# DemoCatV3.net
KiCad netlist of a schematic drawn in Altium Designer
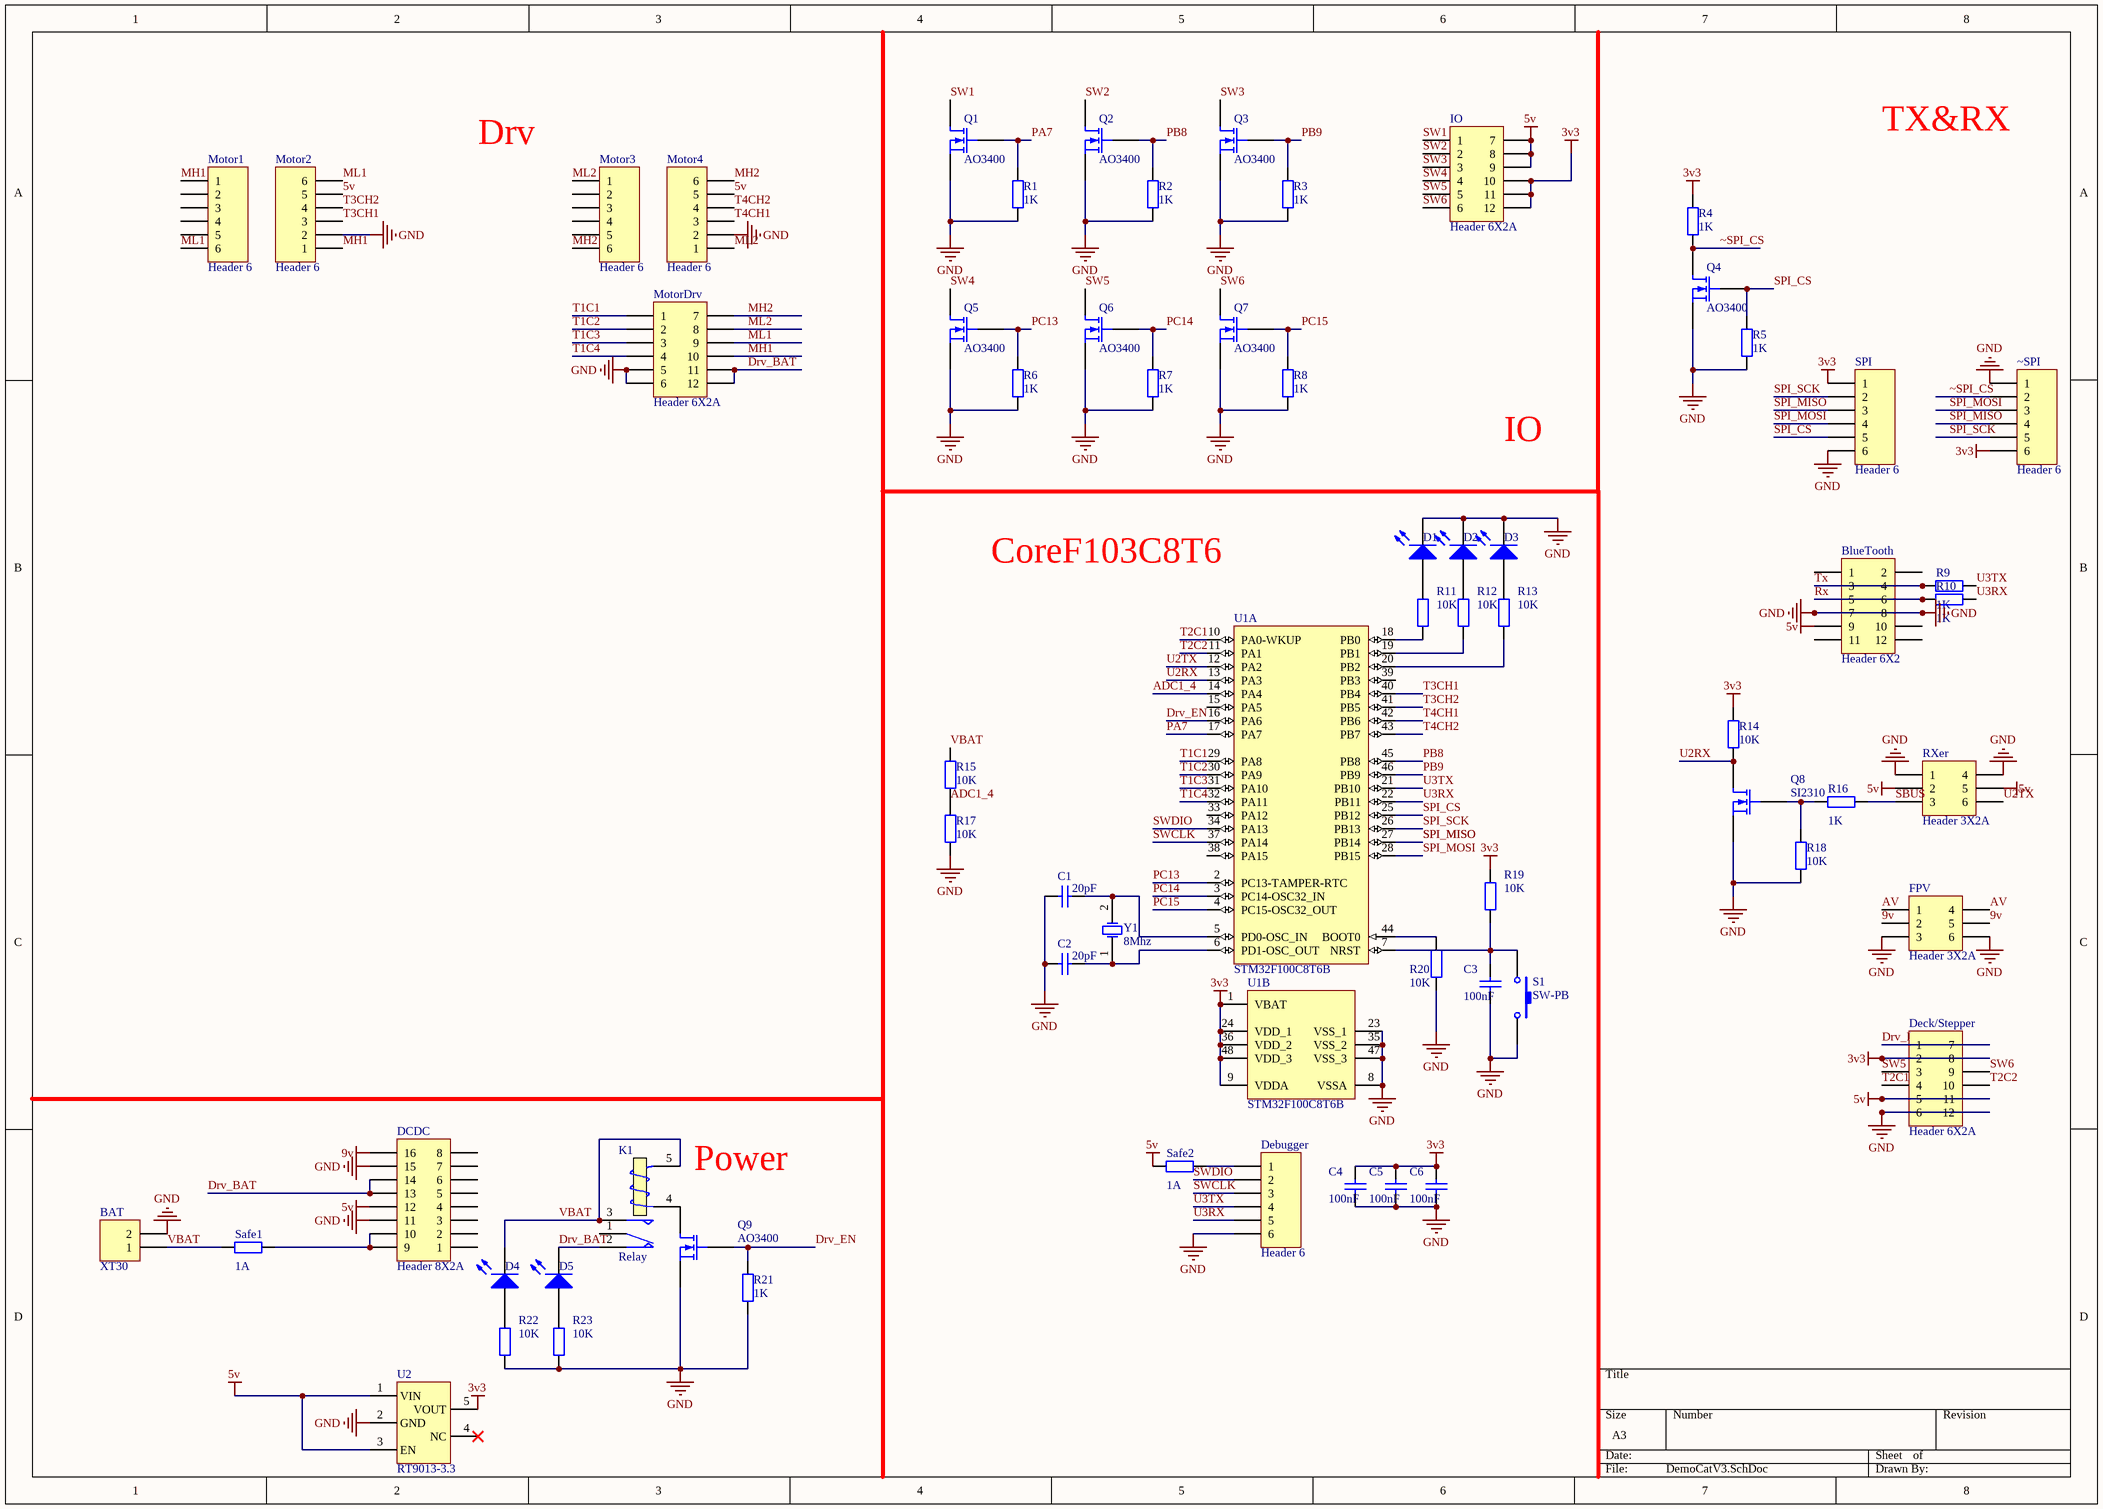
[diagram p0: DemoCatV3.SchDoc]

(export (version "E")
  (design (tool "Eeschema 10.0.6"))
  (components
    (comp (ref "BAT")
      (value "XT30")
      (footprint "XT30-IN-W")
      (description "Header, 2-Pin")
      (fields (field (name "PUBLISHER") "Altium Limited"))
      (libsource (lib "Miscellaneous Connectors") (part "Header 2"))
    )
    (comp (ref "BlueTooth")
      (value "Header 6X2")
      (footprint "HDR2X6")
      (description "Header, 6-Pin, Dual row")
      (fields (field (name "PUBLISHER") "Altium Limited"))
      (libsource (lib "Miscellaneous Connectors") (part "Header 6X2"))
    )
    (comp (ref "C1")
      (value "20pF")
      (footprint "0603C")
      (description "Capacitor")
      (fields (field (name "Comment") "Cap") (field (name "PUBLISHER") "Altium Limited"))
      (libsource (lib "Miscellaneous Devices") (part "Cap"))
    )
    (comp (ref "C2")
      (value "20pF")
      (footprint "0603C")
      (description "Capacitor")
      (fields (field (name "Comment") "Cap") (field (name "PUBLISHER") "Altium Limited"))
      (libsource (lib "Miscellaneous Devices") (part "Cap"))
    )
    (comp (ref "C3")
      (value "100nF")
      (footprint "0603C")
      (description "Capacitor")
      (fields (field (name "Comment") "Cap") (field (name "PUBLISHER") "Altium Limited"))
      (libsource (lib "Miscellaneous Devices") (part "Cap"))
    )
    (comp (ref "C4")
      (value "100nF")
      (footprint "0603C")
      (description "Capacitor")
      (fields (field (name "Comment") "Cap") (field (name "PUBLISHER") "Altium Limited"))
      (libsource (lib "Miscellaneous Devices") (part "Cap"))
    )
    (comp (ref "C5")
      (value "100nF")
      (footprint "0603C")
      (description "Capacitor")
      (fields (field (name "Comment") "Cap") (field (name "PUBLISHER") "Altium Limited"))
      (libsource (lib "Miscellaneous Devices") (part "Cap"))
    )
    (comp (ref "C6")
      (value "100nF")
      (footprint "0603C")
      (description "Capacitor")
      (fields (field (name "Comment") "Cap") (field (name "PUBLISHER") "Altium Limited"))
      (libsource (lib "Miscellaneous Devices") (part "Cap"))
    )
    (comp (ref "D1")
      (value "LED0")
      (footprint "0603LED - Red")
      (description "Typical INFRARED GaAs LED")
      (fields (field (name "PUBLISHER") "Altium Limited"))
      (libsource (lib "Miscellaneous Devices") (part "LED0"))
    )
    (comp (ref "D2")
      (value "LED0")
      (footprint "0603LED - Green")
      (description "Typical INFRARED GaAs LED")
      (fields (field (name "PUBLISHER") "Altium Limited"))
      (libsource (lib "Miscellaneous Devices") (part "LED0"))
    )
    (comp (ref "D3")
      (value "LED0")
      (footprint "0603LED - Blue")
      (description "Typical INFRARED GaAs LED")
      (fields (field (name "PUBLISHER") "Altium Limited"))
      (libsource (lib "Miscellaneous Devices") (part "LED0"))
    )
    (comp (ref "D4")
      (value "LED0")
      (footprint "0603LED - Red")
      (description "Typical INFRARED GaAs LED")
      (fields (field (name "PUBLISHER") "Altium Limited"))
      (libsource (lib "Miscellaneous Devices") (part "LED0"))
    )
    (comp (ref "D5")
      (value "LED0")
      (footprint "0603LED - Red")
      (description "Typical INFRARED GaAs LED")
      (fields (field (name "PUBLISHER") "Altium Limited"))
      (libsource (lib "Miscellaneous Devices") (part "LED0"))
    )
    (comp (ref "DCDC")
      (value "Header 8X2A")
      (footprint "HDR_EDGE_2x8")
      (description "Header, 8-Pin, Dual row")
      (fields (field (name "PUBLISHER") "Altium Limited"))
      (libsource (lib "Miscellaneous Connectors") (part "Header 8X2A"))
    )
    (comp (ref "Debugger")
      (value "Header 6")
      (footprint "GX1.25_T_6P")
      (description "Header, 6-Pin")
      (fields (field (name "PUBLISHER") "Altium Limited"))
      (libsource (lib "Miscellaneous Connectors") (part "Header 6"))
    )
    (comp (ref "Deck/Stepper")
      (value "Header 6X2A")
      (footprint "HDR_EDGE_2x6")
      (description "Header, 6-Pin, Dual row")
      (fields (field (name "PUBLISHER") "Altium Limited"))
      (libsource (lib "Miscellaneous Connectors") (part "Header 6X2A"))
    )
    (comp (ref "FPV")
      (value "Header 3X2A")
      (footprint "HDR_EDGE_2x3")
      (description "Header, 3-Pin, Dual row")
      (fields (field (name "PUBLISHER") "Altium Limited"))
      (libsource (lib "Miscellaneous Connectors") (part "Header 3X2A"))
    )
    (comp (ref "IO")
      (value "Header 6X2A")
      (footprint "HDR_EDGE_2x6")
      (description "Header, 6-Pin, Dual row")
      (fields (field (name "PUBLISHER") "Altium Limited"))
      (libsource (lib "Miscellaneous Connectors") (part "Header 6X2A"))
    )
    (comp (ref "K1")
      (value "Relay")
      (footprint "RY-HF46-HS1")
      (description "SPDT Relay")
      (fields (field (name "PUBLISHER") "Altium Limited"))
      (libsource (lib "Relay") (part "Relay"))
    )
    (comp (ref "Motor1")
      (value "Header 6")
      (footprint "PH-PS-2.0-6")
      (description "Header, 6-Pin")
      (fields (field (name "PUBLISHER") "Altium Limited"))
      (libsource (lib "Miscellaneous Connectors") (part "Header 6"))
    )
    (comp (ref "Motor2")
      (value "Header 6")
      (footprint "PH-PS-2.0-6")
      (description "Header, 6-Pin")
      (fields (field (name "PUBLISHER") "Altium Limited"))
      (libsource (lib "") (part "Header 6_1"))
    )
    (comp (ref "Motor3")
      (value "Header 6")
      (footprint "PH-PS-2.0-6")
      (description "Header, 6-Pin")
      (fields (field (name "PUBLISHER") "Altium Limited"))
      (libsource (lib "Miscellaneous Connectors") (part "Header 6"))
    )
    (comp (ref "Motor4")
      (value "Header 6")
      (footprint "PH-PS-2.0-6")
      (description "Header, 6-Pin")
      (fields (field (name "PUBLISHER") "Altium Limited"))
      (libsource (lib "") (part "Header 6_1"))
    )
    (comp (ref "MotorDrv")
      (value "Header 6X2A")
      (footprint "HDR_EDGE_2x6")
      (description "Header, 6-Pin, Dual row")
      (fields (field (name "PUBLISHER") "Altium Limited"))
      (libsource (lib "Miscellaneous Connectors") (part "Header 6X2A"))
    )
    (comp (ref "Q1")
      (value "AO3400")
      (footprint "SOT-23-MOS")
      (description "N-Channel MOSFET")
      (fields (field (name "PUBLISHER") "Altium Limited"))
      (libsource (lib "Miscellaneous Devices") (part "MOSFET-N"))
    )
    (comp (ref "Q2")
      (value "AO3400")
      (footprint "SOT-23-MOS")
      (description "N-Channel MOSFET")
      (fields (field (name "PUBLISHER") "Altium Limited"))
      (libsource (lib "Miscellaneous Devices") (part "MOSFET-N"))
    )
    (comp (ref "Q3")
      (value "AO3400")
      (footprint "SOT-23-MOS")
      (description "N-Channel MOSFET")
      (fields (field (name "PUBLISHER") "Altium Limited"))
      (libsource (lib "Miscellaneous Devices") (part "MOSFET-N"))
    )
    (comp (ref "Q4")
      (value "AO3400")
      (footprint "SOT-23-MOS")
      (description "N-Channel MOSFET")
      (fields (field (name "PUBLISHER") "Altium Limited"))
      (libsource (lib "Miscellaneous Devices") (part "MOSFET-N"))
    )
    (comp (ref "Q5")
      (value "AO3400")
      (footprint "SOT-23-MOS")
      (description "N-Channel MOSFET")
      (fields (field (name "PUBLISHER") "Altium Limited"))
      (libsource (lib "Miscellaneous Devices") (part "MOSFET-N"))
    )
    (comp (ref "Q6")
      (value "AO3400")
      (footprint "SOT-23-MOS")
      (description "N-Channel MOSFET")
      (fields (field (name "PUBLISHER") "Altium Limited"))
      (libsource (lib "Miscellaneous Devices") (part "MOSFET-N"))
    )
    (comp (ref "Q7")
      (value "AO3400")
      (footprint "SOT-23-MOS")
      (description "N-Channel MOSFET")
      (fields (field (name "PUBLISHER") "Altium Limited"))
      (libsource (lib "Miscellaneous Devices") (part "MOSFET-N"))
    )
    (comp (ref "Q8")
      (value "SI2310")
      (footprint "SOT-23-MOS")
      (description "N-Channel MOSFET")
      (fields (field (name "PUBLISHER") "Altium Limited"))
      (libsource (lib "Miscellaneous Devices") (part "MOSFET-N"))
    )
    (comp (ref "Q9")
      (value "AO3400")
      (footprint "SOT-23-MOS")
      (description "N-Channel MOSFET")
      (fields (field (name "PUBLISHER") "Altium Limited"))
      (libsource (lib "Miscellaneous Devices") (part "MOSFET-N"))
    )
    (comp (ref "R1")
      (value "1K")
      (footprint "0603R")
      (description "Resistor")
      (fields (field (name "Comment") "Res2") (field (name "PUBLISHER") "Altium Limited"))
      (libsource (lib "Miscellaneous Devices") (part "Res2"))
    )
    (comp (ref "R2")
      (value "1K")
      (footprint "0603R")
      (description "Resistor")
      (fields (field (name "Comment") "Res2") (field (name "PUBLISHER") "Altium Limited"))
      (libsource (lib "Miscellaneous Devices") (part "Res2"))
    )
    (comp (ref "R3")
      (value "1K")
      (footprint "0603R")
      (description "Resistor")
      (fields (field (name "Comment") "Res2") (field (name "PUBLISHER") "Altium Limited"))
      (libsource (lib "Miscellaneous Devices") (part "Res2"))
    )
    (comp (ref "R4")
      (value "1K")
      (footprint "0603R")
      (description "Resistor")
      (fields (field (name "Comment") "Res2") (field (name "PUBLISHER") "Altium Limited"))
      (libsource (lib "Miscellaneous Devices") (part "Res2"))
    )
    (comp (ref "R5")
      (value "1K")
      (footprint "0603R")
      (description "Resistor")
      (fields (field (name "Comment") "Res2") (field (name "PUBLISHER") "Altium Limited"))
      (libsource (lib "Miscellaneous Devices") (part "Res2"))
    )
    (comp (ref "R6")
      (value "1K")
      (footprint "0603R")
      (description "Resistor")
      (fields (field (name "Comment") "Res2") (field (name "PUBLISHER") "Altium Limited"))
      (libsource (lib "Miscellaneous Devices") (part "Res2"))
    )
    (comp (ref "R7")
      (value "1K")
      (footprint "0603R")
      (description "Resistor")
      (fields (field (name "Comment") "Res2") (field (name "PUBLISHER") "Altium Limited"))
      (libsource (lib "Miscellaneous Devices") (part "Res2"))
    )
    (comp (ref "R8")
      (value "1K")
      (footprint "0603R")
      (description "Resistor")
      (fields (field (name "Comment") "Res2") (field (name "PUBLISHER") "Altium Limited"))
      (libsource (lib "Miscellaneous Devices") (part "Res2"))
    )
    (comp (ref "R9")
      (value "1K")
      (footprint "0603R")
      (description "Resistor")
      (fields (field (name "Comment") "Res2") (field (name "PUBLISHER") "Altium Limited"))
      (libsource (lib "") (part "Res2_1"))
    )
    (comp (ref "R10")
      (value "1K")
      (footprint "0603R")
      (description "Resistor")
      (fields (field (name "Comment") "Res2") (field (name "PUBLISHER") "Altium Limited"))
      (libsource (lib "") (part "Res2_1"))
    )
    (comp (ref "R11")
      (value "10K")
      (footprint "0603R")
      (description "Resistor")
      (fields (field (name "PUBLISHER") "Altium Limited"))
      (libsource (lib "Miscellaneous Devices") (part "Res2"))
    )
    (comp (ref "R12")
      (value "10K")
      (footprint "0603R")
      (description "Resistor")
      (fields (field (name "PUBLISHER") "Altium Limited"))
      (libsource (lib "Miscellaneous Devices") (part "Res2"))
    )
    (comp (ref "R13")
      (value "10K")
      (footprint "0603R")
      (description "Resistor")
      (fields (field (name "PUBLISHER") "Altium Limited"))
      (libsource (lib "Miscellaneous Devices") (part "Res2"))
    )
    (comp (ref "R14")
      (value "10K")
      (footprint "0603R")
      (description "Resistor")
      (fields (field (name "Comment") "Res2") (field (name "PUBLISHER") "Altium Limited"))
      (libsource (lib "Miscellaneous Devices") (part "Res2"))
    )
    (comp (ref "R15")
      (value "10K")
      (footprint "0603R")
      (description "Resistor")
      (fields (field (name "Comment") "Res2") (field (name "PUBLISHER") "Altium Limited"))
      (libsource (lib "Miscellaneous Devices") (part "Res2"))
    )
    (comp (ref "R16")
      (value "1K")
      (footprint "0603R")
      (description "Resistor")
      (fields (field (name "Comment") "Res2") (field (name "PUBLISHER") "Altium Limited"))
      (libsource (lib "") (part "Res2_1"))
    )
    (comp (ref "R17")
      (value "10K")
      (footprint "0603R")
      (description "Resistor")
      (fields (field (name "Comment") "Res2") (field (name "PUBLISHER") "Altium Limited"))
      (libsource (lib "Miscellaneous Devices") (part "Res2"))
    )
    (comp (ref "R18")
      (value "10K")
      (footprint "0603R")
      (description "Resistor")
      (fields (field (name "Comment") "Res2") (field (name "PUBLISHER") "Altium Limited"))
      (libsource (lib "Miscellaneous Devices") (part "Res2"))
    )
    (comp (ref "R19")
      (value "10K")
      (footprint "0603R")
      (description "Resistor")
      (fields (field (name "PUBLISHER") "Altium Limited"))
      (libsource (lib "Miscellaneous Devices") (part "Res2"))
    )
    (comp (ref "R20")
      (value "10K")
      (footprint "0603R")
      (description "Resistor")
      (fields (field (name "Comment") "Res2") (field (name "PUBLISHER") "Altium Limited"))
      (libsource (lib "Miscellaneous Devices") (part "Res2"))
    )
    (comp (ref "R21")
      (value "1K")
      (footprint "0603R")
      (description "Resistor")
      (fields (field (name "Comment") "Res2") (field (name "PUBLISHER") "Altium Limited"))
      (libsource (lib "Miscellaneous Devices") (part "Res2"))
    )
    (comp (ref "R22")
      (value "10K")
      (footprint "0603R")
      (description "Resistor")
      (fields (field (name "PUBLISHER") "Altium Limited"))
      (libsource (lib "Miscellaneous Devices") (part "Res2"))
    )
    (comp (ref "R23")
      (value "10K")
      (footprint "0603R")
      (description "Resistor")
      (fields (field (name "PUBLISHER") "Altium Limited"))
      (libsource (lib "Miscellaneous Devices") (part "Res2"))
    )
    (comp (ref "RXer")
      (value "Header 3X2A")
      (footprint "HDR_EDGE_2x3")
      (description "Header, 3-Pin, Dual row")
      (fields (field (name "PUBLISHER") "Altium Limited"))
      (libsource (lib "Miscellaneous Connectors") (part "Header 3X2A"))
    )
    (comp (ref "S1")
      (value "SW-PB")
      (footprint "KeySwitch-3X3")
      (description "Switch")
      (fields (field (name "PUBLISHER") "Altium Limited"))
      (libsource (lib "Miscellaneous Devices") (part "SW-PB"))
    )
    (comp (ref "Safe1")
      (value "1A")
      (footprint "Maxwell_LIB:0805R")
      (description "Resistor")
      (fields (field (name "Comment") "Res2") (field (name "PUBLISHER") "Altium Limited"))
      (libsource (lib "") (part "Res2_1"))
    )
    (comp (ref "Safe2")
      (value "1A")
      (footprint "Maxwell_LIB:0805R")
      (description "Resistor")
      (fields (field (name "Comment") "Res2") (field (name "PUBLISHER") "Altium Limited"))
      (libsource (lib "") (part "Res2_1"))
    )
    (comp (ref "SPI")
      (value "Header 6")
      (footprint "GX1.25_T_6P")
      (description "Header, 6-Pin")
      (fields (field (name "PUBLISHER") "Altium Limited"))
      (libsource (lib "Miscellaneous Connectors") (part "Header 6"))
    )
    (comp (ref "U1")
      (value "STM32F100C8T6B")
      (footprint "LQFN-48")
      (libsource (lib "STM32F1") (part "STM32F100C8T6B"))
    )
    (comp (ref "U2")
      (value "RT9013-3.3")
      (footprint "SOT-23-5")
      (description "3.3V 500mA")
      (libsource (lib "My_Library") (part "RT9013"))
    )
    (comp (ref "Y1")
      (value "8Mhz")
      (footprint "OSC 3215-2P")
      (fields (field (name "PUBLISHER") "Altium Limited"))
      (libsource (lib "Miscellaneous Devices") (part "XTAL"))
    )
    (comp (ref "~SPI")
      (value "Header 6")
      (footprint "GX1.25_T_6P")
      (description "Header, 6-Pin")
      (fields (field (name "PUBLISHER") "Altium Limited"))
      (libsource (lib "Miscellaneous Connectors") (part "Header 6"))
    )
  )
  (nets
    (net (code "1") (name "/ADC1_4") (class "Default")
      (node (ref "R15") (pin "1") (pinfunction "1_1") (pintype "passive"))
      (node (ref "R17") (pin "2") (pinfunction "2_2") (pintype "passive"))
      (node (ref "U1") (pin "14") (pinfunction "PA4_14") (pintype "bidirectional"))
    )
    (net (code "2") (name "/AV") (class "Default")
      (node (ref "FPV") (pin "1") (pinfunction "1_1") (pintype "passive"))
      (node (ref "FPV") (pin "4") (pinfunction "4_4") (pintype "passive"))
    )
    (net (code "3") (name "/Drv_BAT") (class "Default")
      (node (ref "D5") (pin "2") (pinfunction "K_2") (pintype "passive"))
      (node (ref "DCDC") (pin "13") (pinfunction "13_13") (pintype "passive"))
      (node (ref "DCDC") (pin "14") (pinfunction "14_14") (pintype "passive"))
      (node (ref "Deck/Stepper") (pin "1") (pinfunction "1_1") (pintype "passive"))
      (node (ref "Deck/Stepper") (pin "7") (pinfunction "7_7") (pintype "passive"))
      (node (ref "K1") (pin "2") (pinfunction "NC_2") (pintype "passive"))
      (node (ref "MotorDrv") (pin "11") (pinfunction "11_11") (pintype "passive"))
      (node (ref "MotorDrv") (pin "12") (pinfunction "12_12") (pintype "passive"))
    )
    (net (code "4") (name "/Drv_EN") (class "Default")
      (node (ref "Q9") (pin "2") (pinfunction "G_2") (pintype "passive"))
      (node (ref "R21") (pin "2") (pinfunction "2_2") (pintype "passive"))
      (node (ref "U1") (pin "16") (pinfunction "PA6_16") (pintype "bidirectional"))
    )
    (net (code "5") (name "/MH1") (class "Default")
      (node (ref "Motor1") (pin "1") (pinfunction "1_1") (pintype "passive"))
      (node (ref "Motor2") (pin "1") (pinfunction "1_1") (pintype "passive"))
      (node (ref "MotorDrv") (pin "10") (pinfunction "10_10") (pintype "passive"))
    )
    (net (code "6") (name "/MH2") (class "Default")
      (node (ref "Motor3") (pin "6") (pinfunction "6_6") (pintype "passive"))
      (node (ref "Motor4") (pin "6") (pinfunction "6_6") (pintype "passive"))
      (node (ref "MotorDrv") (pin "7") (pinfunction "7_7") (pintype "passive"))
    )
    (net (code "7") (name "/ML1") (class "Default")
      (node (ref "Motor1") (pin "6") (pinfunction "6_6") (pintype "passive"))
      (node (ref "Motor2") (pin "6") (pinfunction "6_6") (pintype "passive"))
      (node (ref "MotorDrv") (pin "9") (pinfunction "9_9") (pintype "passive"))
    )
    (net (code "8") (name "/ML2") (class "Default")
      (node (ref "Motor3") (pin "1") (pinfunction "1_1") (pintype "passive"))
      (node (ref "Motor4") (pin "1") (pinfunction "1_1") (pintype "passive"))
      (node (ref "MotorDrv") (pin "8") (pinfunction "8_8") (pintype "passive"))
    )
    (net (code "9") (name "/PA7") (class "Default")
      (node (ref "Q1") (pin "2") (pinfunction "G_2") (pintype "passive"))
      (node (ref "R1") (pin "2") (pinfunction "2_2") (pintype "passive"))
      (node (ref "U1") (pin "17") (pinfunction "PA7_17") (pintype "bidirectional"))
    )
    (net (code "10") (name "/PB8") (class "Default")
      (node (ref "Q2") (pin "2") (pinfunction "G_2") (pintype "passive"))
      (node (ref "R2") (pin "2") (pinfunction "2_2") (pintype "passive"))
      (node (ref "U1") (pin "45") (pinfunction "PB8_45") (pintype "bidirectional"))
    )
    (net (code "11") (name "/PB9") (class "Default")
      (node (ref "Q3") (pin "2") (pinfunction "G_2") (pintype "passive"))
      (node (ref "R3") (pin "2") (pinfunction "2_2") (pintype "passive"))
      (node (ref "U1") (pin "46") (pinfunction "PB9_46") (pintype "bidirectional"))
    )
    (net (code "12") (name "/PC13") (class "Default")
      (node (ref "Q5") (pin "2") (pinfunction "G_2") (pintype "passive"))
      (node (ref "R6") (pin "2") (pinfunction "2_2") (pintype "passive"))
      (node (ref "U1") (pin "2") (pinfunction "PC13-TAMPER-RTC_2") (pintype "bidirectional"))
    )
    (net (code "13") (name "/PC14") (class "Default")
      (node (ref "Q6") (pin "2") (pinfunction "G_2") (pintype "passive"))
      (node (ref "R7") (pin "2") (pinfunction "2_2") (pintype "passive"))
      (node (ref "U1") (pin "3") (pinfunction "PC14-OSC32_IN_3") (pintype "bidirectional"))
    )
    (net (code "14") (name "/PC15") (class "Default")
      (node (ref "Q7") (pin "2") (pinfunction "G_2") (pintype "passive"))
      (node (ref "R8") (pin "2") (pinfunction "2_2") (pintype "passive"))
      (node (ref "U1") (pin "4") (pinfunction "PC15-OSC32_OUT_4") (pintype "bidirectional"))
    )
    (net (code "15") (name "/Rx") (class "Default")
      (node (ref "BlueTooth") (pin "5") (pinfunction "5_5") (pintype "passive"))
      (node (ref "BlueTooth") (pin "6") (pinfunction "6_6") (pintype "passive"))
      (node (ref "R10") (pin "1") (pinfunction "1_1") (pintype "passive"))
    )
    (net (code "16") (name "/SBUS") (class "Default")
      (node (ref "R16") (pin "2") (pinfunction "2_2") (pintype "passive"))
      (node (ref "RXer") (pin "3") (pinfunction "3_3") (pintype "passive"))
    )
    (net (code "17") (name "/SPI_CS") (class "Default")
      (node (ref "Q4") (pin "2") (pinfunction "G_2") (pintype "passive"))
      (node (ref "R5") (pin "2") (pinfunction "2_2") (pintype "passive"))
      (node (ref "SPI") (pin "5") (pinfunction "5_5") (pintype "passive"))
      (node (ref "U1") (pin "25") (pinfunction "PB12_25") (pintype "bidirectional"))
    )
    (net (code "18") (name "/SPI_MISO") (class "Default")
      (node (ref "SPI") (pin "3") (pinfunction "3_3") (pintype "passive"))
      (node (ref "U1") (pin "27") (pinfunction "PB14_27") (pintype "bidirectional"))
      (node (ref "~SPI") (pin "4") (pinfunction "4_4") (pintype "passive"))
    )
    (net (code "19") (name "/SPI_MOSI") (class "Default")
      (node (ref "SPI") (pin "4") (pinfunction "4_4") (pintype "passive"))
      (node (ref "U1") (pin "28") (pinfunction "PB15_28") (pintype "bidirectional"))
      (node (ref "~SPI") (pin "3") (pinfunction "3_3") (pintype "passive"))
    )
    (net (code "20") (name "/SPI_SCK") (class "Default")
      (node (ref "SPI") (pin "2") (pinfunction "2_2") (pintype "passive"))
      (node (ref "U1") (pin "26") (pinfunction "PB13_26") (pintype "bidirectional"))
      (node (ref "~SPI") (pin "5") (pinfunction "5_5") (pintype "passive"))
    )
    (net (code "21") (name "/SW1") (class "Default")
      (node (ref "IO") (pin "1") (pinfunction "1_1") (pintype "passive"))
      (node (ref "Q1") (pin "1") (pinfunction "D_1") (pintype "passive"))
    )
    (net (code "22") (name "/SW2") (class "Default")
      (node (ref "IO") (pin "2") (pinfunction "2_2") (pintype "passive"))
      (node (ref "Q2") (pin "1") (pinfunction "D_1") (pintype "passive"))
    )
    (net (code "23") (name "/SW3") (class "Default")
      (node (ref "IO") (pin "3") (pinfunction "3_3") (pintype "passive"))
      (node (ref "Q3") (pin "1") (pinfunction "D_1") (pintype "passive"))
    )
    (net (code "24") (name "/SW4") (class "Default")
      (node (ref "IO") (pin "4") (pinfunction "4_4") (pintype "passive"))
      (node (ref "Q5") (pin "1") (pinfunction "D_1") (pintype "passive"))
    )
    (net (code "25") (name "/SW5") (class "Default")
      (node (ref "Deck/Stepper") (pin "3") (pinfunction "3_3") (pintype "passive"))
      (node (ref "IO") (pin "5") (pinfunction "5_5") (pintype "passive"))
      (node (ref "Q6") (pin "1") (pinfunction "D_1") (pintype "passive"))
    )
    (net (code "26") (name "/SW6") (class "Default")
      (node (ref "Deck/Stepper") (pin "9") (pinfunction "9_9") (pintype "passive"))
      (node (ref "IO") (pin "6") (pinfunction "6_6") (pintype "passive"))
      (node (ref "Q7") (pin "1") (pinfunction "D_1") (pintype "passive"))
    )
    (net (code "27") (name "/SWCLK") (class "Default")
      (node (ref "Debugger") (pin "3") (pinfunction "3_3") (pintype "passive"))
      (node (ref "U1") (pin "37") (pinfunction "PA14_37") (pintype "bidirectional"))
    )
    (net (code "28") (name "/SWDIO") (class "Default")
      (node (ref "Debugger") (pin "2") (pinfunction "2_2") (pintype "passive"))
      (node (ref "U1") (pin "34") (pinfunction "PA13_34") (pintype "bidirectional"))
    )
    (net (code "29") (name "/T1C1") (class "Default")
      (node (ref "MotorDrv") (pin "1") (pinfunction "1_1") (pintype "passive"))
      (node (ref "U1") (pin "29") (pinfunction "PA8_29") (pintype "bidirectional"))
    )
    (net (code "30") (name "/T1C2") (class "Default")
      (node (ref "MotorDrv") (pin "2") (pinfunction "2_2") (pintype "passive"))
      (node (ref "U1") (pin "30") (pinfunction "PA9_30") (pintype "bidirectional"))
    )
    (net (code "31") (name "/T1C3") (class "Default")
      (node (ref "MotorDrv") (pin "3") (pinfunction "3_3") (pintype "passive"))
      (node (ref "U1") (pin "31") (pinfunction "PA10_31") (pintype "bidirectional"))
    )
    (net (code "32") (name "/T1C4") (class "Default")
      (node (ref "MotorDrv") (pin "4") (pinfunction "4_4") (pintype "passive"))
      (node (ref "U1") (pin "32") (pinfunction "PA11_32") (pintype "bidirectional"))
    )
    (net (code "33") (name "/T2C1") (class "Default")
      (node (ref "Deck/Stepper") (pin "4") (pinfunction "4_4") (pintype "passive"))
      (node (ref "U1") (pin "10") (pinfunction "PA0-WKUP_10") (pintype "bidirectional"))
    )
    (net (code "34") (name "/T2C2") (class "Default")
      (node (ref "Deck/Stepper") (pin "10") (pinfunction "10_10") (pintype "passive"))
      (node (ref "U1") (pin "11") (pinfunction "PA1_11") (pintype "bidirectional"))
    )
    (net (code "35") (name "/T3CH1") (class "Default")
      (node (ref "Motor2") (pin "3") (pinfunction "3_3") (pintype "passive"))
      (node (ref "U1") (pin "40") (pinfunction "PB4_40") (pintype "bidirectional"))
    )
    (net (code "36") (name "/T3CH2") (class "Default")
      (node (ref "Motor2") (pin "4") (pinfunction "4_4") (pintype "passive"))
      (node (ref "U1") (pin "41") (pinfunction "PB5_41") (pintype "bidirectional"))
    )
    (net (code "37") (name "/T4CH1") (class "Default")
      (node (ref "Motor4") (pin "3") (pinfunction "3_3") (pintype "passive"))
      (node (ref "U1") (pin "42") (pinfunction "PB6_42") (pintype "bidirectional"))
    )
    (net (code "38") (name "/T4CH2") (class "Default")
      (node (ref "Motor4") (pin "4") (pinfunction "4_4") (pintype "passive"))
      (node (ref "U1") (pin "43") (pinfunction "PB7_43") (pintype "bidirectional"))
    )
    (net (code "39") (name "/Tx") (class "Default")
      (node (ref "BlueTooth") (pin "3") (pinfunction "3_3") (pintype "passive"))
      (node (ref "BlueTooth") (pin "4") (pinfunction "4_4") (pintype "passive"))
      (node (ref "R9") (pin "1") (pinfunction "1_1") (pintype "passive"))
    )
    (net (code "40") (name "/U2RX") (class "Default")
      (node (ref "Q8") (pin "1") (pinfunction "D_1") (pintype "passive"))
      (node (ref "R14") (pin "1") (pinfunction "1_1") (pintype "passive"))
      (node (ref "U1") (pin "13") (pinfunction "PA3_13") (pintype "bidirectional"))
    )
    (net (code "41") (name "/U2TX") (class "Default")
      (node (ref "RXer") (pin "6") (pinfunction "6_6") (pintype "passive"))
      (node (ref "U1") (pin "12") (pinfunction "PA2_12") (pintype "bidirectional"))
    )
    (net (code "42") (name "/U3RX") (class "Default")
      (node (ref "Debugger") (pin "5") (pinfunction "5_5") (pintype "passive"))
      (node (ref "R10") (pin "2") (pinfunction "2_2") (pintype "passive"))
      (node (ref "U1") (pin "22") (pinfunction "PB11_22") (pintype "bidirectional"))
    )
    (net (code "43") (name "/U3TX") (class "Default")
      (node (ref "Debugger") (pin "4") (pinfunction "4_4") (pintype "passive"))
      (node (ref "R9") (pin "2") (pinfunction "2_2") (pintype "passive"))
      (node (ref "U1") (pin "21") (pinfunction "PB10_21") (pintype "bidirectional"))
    )
    (net (code "44") (name "/VBAT") (class "Default")
      (node (ref "BAT") (pin "1") (pinfunction "1_1") (pintype "passive"))
      (node (ref "D4") (pin "2") (pinfunction "K_2") (pintype "passive"))
      (node (ref "K1") (pin "3") (pinfunction "NO_3") (pintype "passive"))
      (node (ref "K1") (pin "5") (pinfunction "T2_5") (pintype "passive"))
      (node (ref "R15") (pin "2") (pinfunction "2_2") (pintype "passive"))
      (node (ref "Safe1") (pin "1") (pinfunction "1_1") (pintype "passive"))
    )
    (net (code "45") (name "/~SPI_CS") (class "Default")
      (node (ref "Q4") (pin "1") (pinfunction "D_1") (pintype "passive"))
      (node (ref "R4") (pin "1") (pinfunction "1_1") (pintype "passive"))
      (node (ref "~SPI") (pin "2") (pinfunction "2_2") (pintype "passive"))
    )
    (net (code "46") (name "3v3") (class "Default")
      (node (ref "C4") (pin "2") (pinfunction "2_2") (pintype "passive"))
      (node (ref "C5") (pin "2") (pinfunction "2_2") (pintype "passive"))
      (node (ref "C6") (pin "2") (pinfunction "2_2") (pintype "passive"))
      (node (ref "Deck/Stepper") (pin "2") (pinfunction "2_2") (pintype "passive"))
      (node (ref "Deck/Stepper") (pin "8") (pinfunction "8_8") (pintype "passive"))
      (node (ref "IO") (pin "10") (pinfunction "10_10") (pintype "passive"))
      (node (ref "IO") (pin "11") (pinfunction "11_11") (pintype "passive"))
      (node (ref "IO") (pin "12") (pinfunction "12_12") (pintype "passive"))
      (node (ref "R14") (pin "2") (pinfunction "2_2") (pintype "passive"))
      (node (ref "R19") (pin "2") (pinfunction "2_2") (pintype "passive"))
      (node (ref "R4") (pin "2") (pinfunction "2_2") (pintype "passive"))
      (node (ref "SPI") (pin "1") (pinfunction "1_1") (pintype "passive"))
      (node (ref "U1") (pin "1") (pinfunction "VBAT_1") (pintype "power_in"))
      (node (ref "U1") (pin "24") (pinfunction "VDD_1_24") (pintype "power_in"))
      (node (ref "U1") (pin "36") (pinfunction "VDD_2_36") (pintype "power_in"))
      (node (ref "U1") (pin "48") (pinfunction "VDD_3_48") (pintype "power_in"))
      (node (ref "U1") (pin "9") (pinfunction "VDDA_9") (pintype "power_in"))
      (node (ref "U2") (pin "5") (pinfunction "VOUT_5") (pintype "passive"))
      (node (ref "~SPI") (pin "6") (pinfunction "6_6") (pintype "passive"))
    )
    (net (code "47") (name "5v") (class "Default")
      (node (ref "BlueTooth") (pin "9") (pinfunction "9_9") (pintype "passive"))
      (node (ref "DCDC") (pin "12") (pinfunction "12_12") (pintype "passive"))
      (node (ref "Deck/Stepper") (pin "11") (pinfunction "11_11") (pintype "passive"))
      (node (ref "Deck/Stepper") (pin "5") (pinfunction "5_5") (pintype "passive"))
      (node (ref "IO") (pin "7") (pinfunction "7_7") (pintype "passive"))
      (node (ref "IO") (pin "8") (pinfunction "8_8") (pintype "passive"))
      (node (ref "IO") (pin "9") (pinfunction "9_9") (pintype "passive"))
      (node (ref "Motor2") (pin "5") (pinfunction "5_5") (pintype "passive"))
      (node (ref "Motor4") (pin "5") (pinfunction "5_5") (pintype "passive"))
      (node (ref "RXer") (pin "2") (pinfunction "2_2") (pintype "passive"))
      (node (ref "RXer") (pin "5") (pinfunction "5_5") (pintype "passive"))
      (node (ref "Safe2") (pin "1") (pinfunction "1_1") (pintype "passive"))
      (node (ref "U2") (pin "1") (pinfunction "VIN_1") (pintype "passive"))
      (node (ref "U2") (pin "3") (pinfunction "EN_3") (pintype "passive"))
    )
    (net (code "48") (name "9v") (class "Default")
      (node (ref "DCDC") (pin "16") (pinfunction "16_16") (pintype "passive"))
      (node (ref "FPV") (pin "2") (pinfunction "2_2") (pintype "passive"))
      (node (ref "FPV") (pin "5") (pinfunction "5_5") (pintype "passive"))
    )
    (net (code "49") (name "GND") (class "Default")
      (node (ref "BAT") (pin "2") (pinfunction "2_2") (pintype "passive"))
      (node (ref "BlueTooth") (pin "7") (pinfunction "7_7") (pintype "passive"))
      (node (ref "BlueTooth") (pin "8") (pinfunction "8_8") (pintype "passive"))
      (node (ref "C1") (pin "1") (pinfunction "1_1") (pintype "passive"))
      (node (ref "C2") (pin "1") (pinfunction "1_1") (pintype "passive"))
      (node (ref "C3") (pin "1") (pinfunction "1_1") (pintype "passive"))
      (node (ref "C4") (pin "1") (pinfunction "1_1") (pintype "passive"))
      (node (ref "C5") (pin "1") (pinfunction "1_1") (pintype "passive"))
      (node (ref "C6") (pin "1") (pinfunction "1_1") (pintype "passive"))
      (node (ref "D1") (pin "2") (pinfunction "K_2") (pintype "passive"))
      (node (ref "D2") (pin "2") (pinfunction "K_2") (pintype "passive"))
      (node (ref "D3") (pin "2") (pinfunction "K_2") (pintype "passive"))
      (node (ref "DCDC") (pin "11") (pinfunction "11_11") (pintype "passive"))
      (node (ref "DCDC") (pin "15") (pinfunction "15_15") (pintype "passive"))
      (node (ref "Debugger") (pin "6") (pinfunction "6_6") (pintype "passive"))
      (node (ref "Deck/Stepper") (pin "12") (pinfunction "12_12") (pintype "passive"))
      (node (ref "Deck/Stepper") (pin "6") (pinfunction "6_6") (pintype "passive"))
      (node (ref "FPV") (pin "3") (pinfunction "3_3") (pintype "passive"))
      (node (ref "FPV") (pin "6") (pinfunction "6_6") (pintype "passive"))
      (node (ref "Motor2") (pin "2") (pinfunction "2_2") (pintype "passive"))
      (node (ref "Motor4") (pin "2") (pinfunction "2_2") (pintype "passive"))
      (node (ref "MotorDrv") (pin "5") (pinfunction "5_5") (pintype "passive"))
      (node (ref "MotorDrv") (pin "6") (pinfunction "6_6") (pintype "passive"))
      (node (ref "Q1") (pin "3") (pinfunction "S_3") (pintype "passive"))
      (node (ref "Q2") (pin "3") (pinfunction "S_3") (pintype "passive"))
      (node (ref "Q3") (pin "3") (pinfunction "S_3") (pintype "passive"))
      (node (ref "Q4") (pin "3") (pinfunction "S_3") (pintype "passive"))
      (node (ref "Q5") (pin "3") (pinfunction "S_3") (pintype "passive"))
      (node (ref "Q6") (pin "3") (pinfunction "S_3") (pintype "passive"))
      (node (ref "Q7") (pin "3") (pinfunction "S_3") (pintype "passive"))
      (node (ref "Q8") (pin "3") (pinfunction "S_3") (pintype "passive"))
      (node (ref "Q9") (pin "3") (pinfunction "S_3") (pintype "passive"))
      (node (ref "R1") (pin "1") (pinfunction "1_1") (pintype "passive"))
      (node (ref "R17") (pin "1") (pinfunction "1_1") (pintype "passive"))
      (node (ref "R18") (pin "1") (pinfunction "1_1") (pintype "passive"))
      (node (ref "R2") (pin "1") (pinfunction "1_1") (pintype "passive"))
      (node (ref "R20") (pin "1") (pinfunction "1_1") (pintype "passive"))
      (node (ref "R21") (pin "1") (pinfunction "1_1") (pintype "passive"))
      (node (ref "R22") (pin "1") (pinfunction "1_1") (pintype "passive"))
      (node (ref "R23") (pin "1") (pinfunction "1_1") (pintype "passive"))
      (node (ref "R3") (pin "1") (pinfunction "1_1") (pintype "passive"))
      (node (ref "R5") (pin "1") (pinfunction "1_1") (pintype "passive"))
      (node (ref "R6") (pin "1") (pinfunction "1_1") (pintype "passive"))
      (node (ref "R7") (pin "1") (pinfunction "1_1") (pintype "passive"))
      (node (ref "R8") (pin "1") (pinfunction "1_1") (pintype "passive"))
      (node (ref "RXer") (pin "1") (pinfunction "1_1") (pintype "passive"))
      (node (ref "RXer") (pin "4") (pinfunction "4_4") (pintype "passive"))
      (node (ref "S1") (pin "2") (pinfunction "2_2") (pintype "passive"))
      (node (ref "SPI") (pin "6") (pinfunction "6_6") (pintype "passive"))
      (node (ref "U1") (pin "23") (pinfunction "VSS_1_23") (pintype "power_in"))
      (node (ref "U1") (pin "35") (pinfunction "VSS_2_35") (pintype "power_in"))
      (node (ref "U1") (pin "47") (pinfunction "VSS_3_47") (pintype "power_in"))
      (node (ref "U1") (pin "8") (pinfunction "VSSA_8") (pintype "power_in"))
      (node (ref "U2") (pin "2") (pinfunction "GND_2") (pintype "passive"))
      (node (ref "~SPI") (pin "1") (pinfunction "1_1") (pintype "passive"))
    )
    (net (code "50") (name "Net-(D1-A)") (class "Default")
      (node (ref "D1") (pin "1") (pinfunction "A_1") (pintype "passive"))
      (node (ref "R11") (pin "2") (pinfunction "2_2") (pintype "passive"))
    )
    (net (code "51") (name "Net-(D2-A)") (class "Default")
      (node (ref "D2") (pin "1") (pinfunction "A_1") (pintype "passive"))
      (node (ref "R12") (pin "2") (pinfunction "2_2") (pintype "passive"))
    )
    (net (code "52") (name "Net-(D3-A)") (class "Default")
      (node (ref "D3") (pin "1") (pinfunction "A_1") (pintype "passive"))
      (node (ref "R13") (pin "2") (pinfunction "2_2") (pintype "passive"))
    )
    (net (code "53") (name "Net-(D4-A)") (class "Default")
      (node (ref "D4") (pin "1") (pinfunction "A_1") (pintype "passive"))
      (node (ref "R22") (pin "2") (pinfunction "2_2") (pintype "passive"))
    )
    (net (code "54") (name "Net-(D5-A)") (class "Default")
      (node (ref "D5") (pin "1") (pinfunction "A_1") (pintype "passive"))
      (node (ref "R23") (pin "2") (pinfunction "2_2") (pintype "passive"))
    )
    (net (code "55") (name "Net-(DCDC-Pad10)") (class "Default")
      (node (ref "DCDC") (pin "10") (pinfunction "10_10") (pintype "passive"))
      (node (ref "DCDC") (pin "9") (pinfunction "9_9") (pintype "passive"))
      (node (ref "Safe1") (pin "2") (pinfunction "2_2") (pintype "passive"))
    )
    (net (code "56") (name "Net-(Debugger-Pad1)") (class "Default")
      (node (ref "Debugger") (pin "1") (pinfunction "1_1") (pintype "passive"))
      (node (ref "Safe2") (pin "2") (pinfunction "2_2") (pintype "passive"))
    )
    (net (code "57") (name "Net-(K1-T1)") (class "Default")
      (node (ref "K1") (pin "4") (pinfunction "T1_4") (pintype "passive"))
      (node (ref "Q9") (pin "1") (pinfunction "D_1") (pintype "passive"))
    )
    (net (code "58") (name "Net-(Q8-G)") (class "Default")
      (node (ref "Q8") (pin "2") (pinfunction "G_2") (pintype "passive"))
      (node (ref "R16") (pin "1") (pinfunction "1_1") (pintype "passive"))
      (node (ref "R18") (pin "2") (pinfunction "2_2") (pintype "passive"))
    )
    (net (code "59") (name "Net-(U1A-BOOT0)") (class "Default")
      (node (ref "R20") (pin "2") (pinfunction "2_2") (pintype "passive"))
      (node (ref "U1") (pin "44") (pinfunction "BOOT0_44") (pintype "input"))
    )
    (net (code "60") (name "Net-(U1A-NRST)") (class "Default")
      (node (ref "C3") (pin "2") (pinfunction "2_2") (pintype "passive"))
      (node (ref "R19") (pin "1") (pinfunction "1_1") (pintype "passive"))
      (node (ref "S1") (pin "1") (pinfunction "1_1") (pintype "passive"))
      (node (ref "U1") (pin "7") (pinfunction "NRST_7") (pintype "bidirectional"))
    )
    (net (code "61") (name "Net-(U1A-PB0)") (class "Default")
      (node (ref "R11") (pin "1") (pinfunction "1_1") (pintype "passive"))
      (node (ref "U1") (pin "18") (pinfunction "PB0_18") (pintype "bidirectional"))
    )
    (net (code "62") (name "Net-(U1A-PB1)") (class "Default")
      (node (ref "R12") (pin "1") (pinfunction "1_1") (pintype "passive"))
      (node (ref "U1") (pin "19") (pinfunction "PB1_19") (pintype "bidirectional"))
    )
    (net (code "63") (name "Net-(U1A-PB2)") (class "Default")
      (node (ref "R13") (pin "1") (pinfunction "1_1") (pintype "passive"))
      (node (ref "U1") (pin "20") (pinfunction "PB2_20") (pintype "bidirectional"))
    )
    (net (code "64") (name "Net-(U1A-PD0-OSC_IN)") (class "Default")
      (node (ref "C1") (pin "2") (pinfunction "2_2") (pintype "passive"))
      (node (ref "U1") (pin "5") (pinfunction "PD0-OSC_IN_5") (pintype "bidirectional"))
      (node (ref "Y1") (pin "2") (pinfunction "OSC2_2") (pintype "passive"))
    )
    (net (code "65") (name "Net-(U1A-PD1-OSC_OUT)") (class "Default")
      (node (ref "C2") (pin "2") (pinfunction "2_2") (pintype "passive"))
      (node (ref "U1") (pin "6") (pinfunction "PD1-OSC_OUT_6") (pintype "bidirectional"))
      (node (ref "Y1") (pin "1") (pinfunction "OSC1_1") (pintype "passive"))
    )
    (net (code "66") (name "unconnected-(BlueTooth-Pad1)") (class "Default")
      (node (ref "BlueTooth") (pin "1") (pinfunction "1_1") (pintype "passive"))
    )
    (net (code "67") (name "unconnected-(BlueTooth-Pad2)") (class "Default")
      (node (ref "BlueTooth") (pin "2") (pinfunction "2_2") (pintype "passive"))
    )
    (net (code "68") (name "unconnected-(BlueTooth-Pad10)") (class "Default")
      (node (ref "BlueTooth") (pin "10") (pinfunction "10_10") (pintype "passive"))
    )
    (net (code "69") (name "unconnected-(BlueTooth-Pad11)") (class "Default")
      (node (ref "BlueTooth") (pin "11") (pinfunction "11_11") (pintype "passive"))
    )
    (net (code "70") (name "unconnected-(BlueTooth-Pad12)") (class "Default")
      (node (ref "BlueTooth") (pin "12") (pinfunction "12_12") (pintype "passive"))
    )
    (net (code "71") (name "unconnected-(DCDC-Pad1)") (class "Default")
      (node (ref "DCDC") (pin "1") (pinfunction "1_1") (pintype "passive"))
    )
    (net (code "72") (name "unconnected-(DCDC-Pad2)") (class "Default")
      (node (ref "DCDC") (pin "2") (pinfunction "2_2") (pintype "passive"))
    )
    (net (code "73") (name "unconnected-(DCDC-Pad3)") (class "Default")
      (node (ref "DCDC") (pin "3") (pinfunction "3_3") (pintype "passive"))
    )
    (net (code "74") (name "unconnected-(DCDC-Pad4)") (class "Default")
      (node (ref "DCDC") (pin "4") (pinfunction "4_4") (pintype "passive"))
    )
    (net (code "75") (name "unconnected-(DCDC-Pad5)") (class "Default")
      (node (ref "DCDC") (pin "5") (pinfunction "5_5") (pintype "passive"))
    )
    (net (code "76") (name "unconnected-(DCDC-Pad6)") (class "Default")
      (node (ref "DCDC") (pin "6") (pinfunction "6_6") (pintype "passive"))
    )
    (net (code "77") (name "unconnected-(DCDC-Pad7)") (class "Default")
      (node (ref "DCDC") (pin "7") (pinfunction "7_7") (pintype "passive"))
    )
    (net (code "78") (name "unconnected-(DCDC-Pad8)") (class "Default")
      (node (ref "DCDC") (pin "8") (pinfunction "8_8") (pintype "passive"))
    )
    (net (code "79") (name "unconnected-(K1-COM-Pad1)") (class "Default")
      (node (ref "K1") (pin "1") (pinfunction "COM_1") (pintype "passive"))
    )
    (net (code "80") (name "unconnected-(Motor1-Pad2)") (class "Default")
      (node (ref "Motor1") (pin "2") (pinfunction "2_2") (pintype "passive"))
    )
    (net (code "81") (name "unconnected-(Motor1-Pad3)") (class "Default")
      (node (ref "Motor1") (pin "3") (pinfunction "3_3") (pintype "passive"))
    )
    (net (code "82") (name "unconnected-(Motor1-Pad4)") (class "Default")
      (node (ref "Motor1") (pin "4") (pinfunction "4_4") (pintype "passive"))
    )
    (net (code "83") (name "unconnected-(Motor1-Pad5)") (class "Default")
      (node (ref "Motor1") (pin "5") (pinfunction "5_5") (pintype "passive"))
    )
    (net (code "84") (name "unconnected-(Motor3-Pad2)") (class "Default")
      (node (ref "Motor3") (pin "2") (pinfunction "2_2") (pintype "passive"))
    )
    (net (code "85") (name "unconnected-(Motor3-Pad3)") (class "Default")
      (node (ref "Motor3") (pin "3") (pinfunction "3_3") (pintype "passive"))
    )
    (net (code "86") (name "unconnected-(Motor3-Pad4)") (class "Default")
      (node (ref "Motor3") (pin "4") (pinfunction "4_4") (pintype "passive"))
    )
    (net (code "87") (name "unconnected-(Motor3-Pad5)") (class "Default")
      (node (ref "Motor3") (pin "5") (pinfunction "5_5") (pintype "passive"))
    )
    (net (code "88") (name "unconnected-(U1A-PA5-Pad15)") (class "Default")
      (node (ref "U1") (pin "15") (pinfunction "PA5_15") (pintype "bidirectional"))
    )
    (net (code "89") (name "unconnected-(U1A-PA12-Pad33)") (class "Default")
      (node (ref "U1") (pin "33") (pinfunction "PA12_33") (pintype "bidirectional"))
    )
    (net (code "90") (name "unconnected-(U1A-PA15-Pad38)") (class "Default")
      (node (ref "U1") (pin "38") (pinfunction "PA15_38") (pintype "bidirectional"))
    )
    (net (code "91") (name "unconnected-(U1A-PB3-Pad39)") (class "Default")
      (node (ref "U1") (pin "39") (pinfunction "PB3_39") (pintype "bidirectional"))
    )
    (net (code "92") (name "unconnected-(U2-NC-Pad4)") (class "Default")
      (node (ref "U2") (pin "4") (pinfunction "NC_4") (pintype "passive+no_connect"))
    )
  )
)
